# BeanCounter_V10.net
KiCad netlist of a schematic drawn in EAGLE
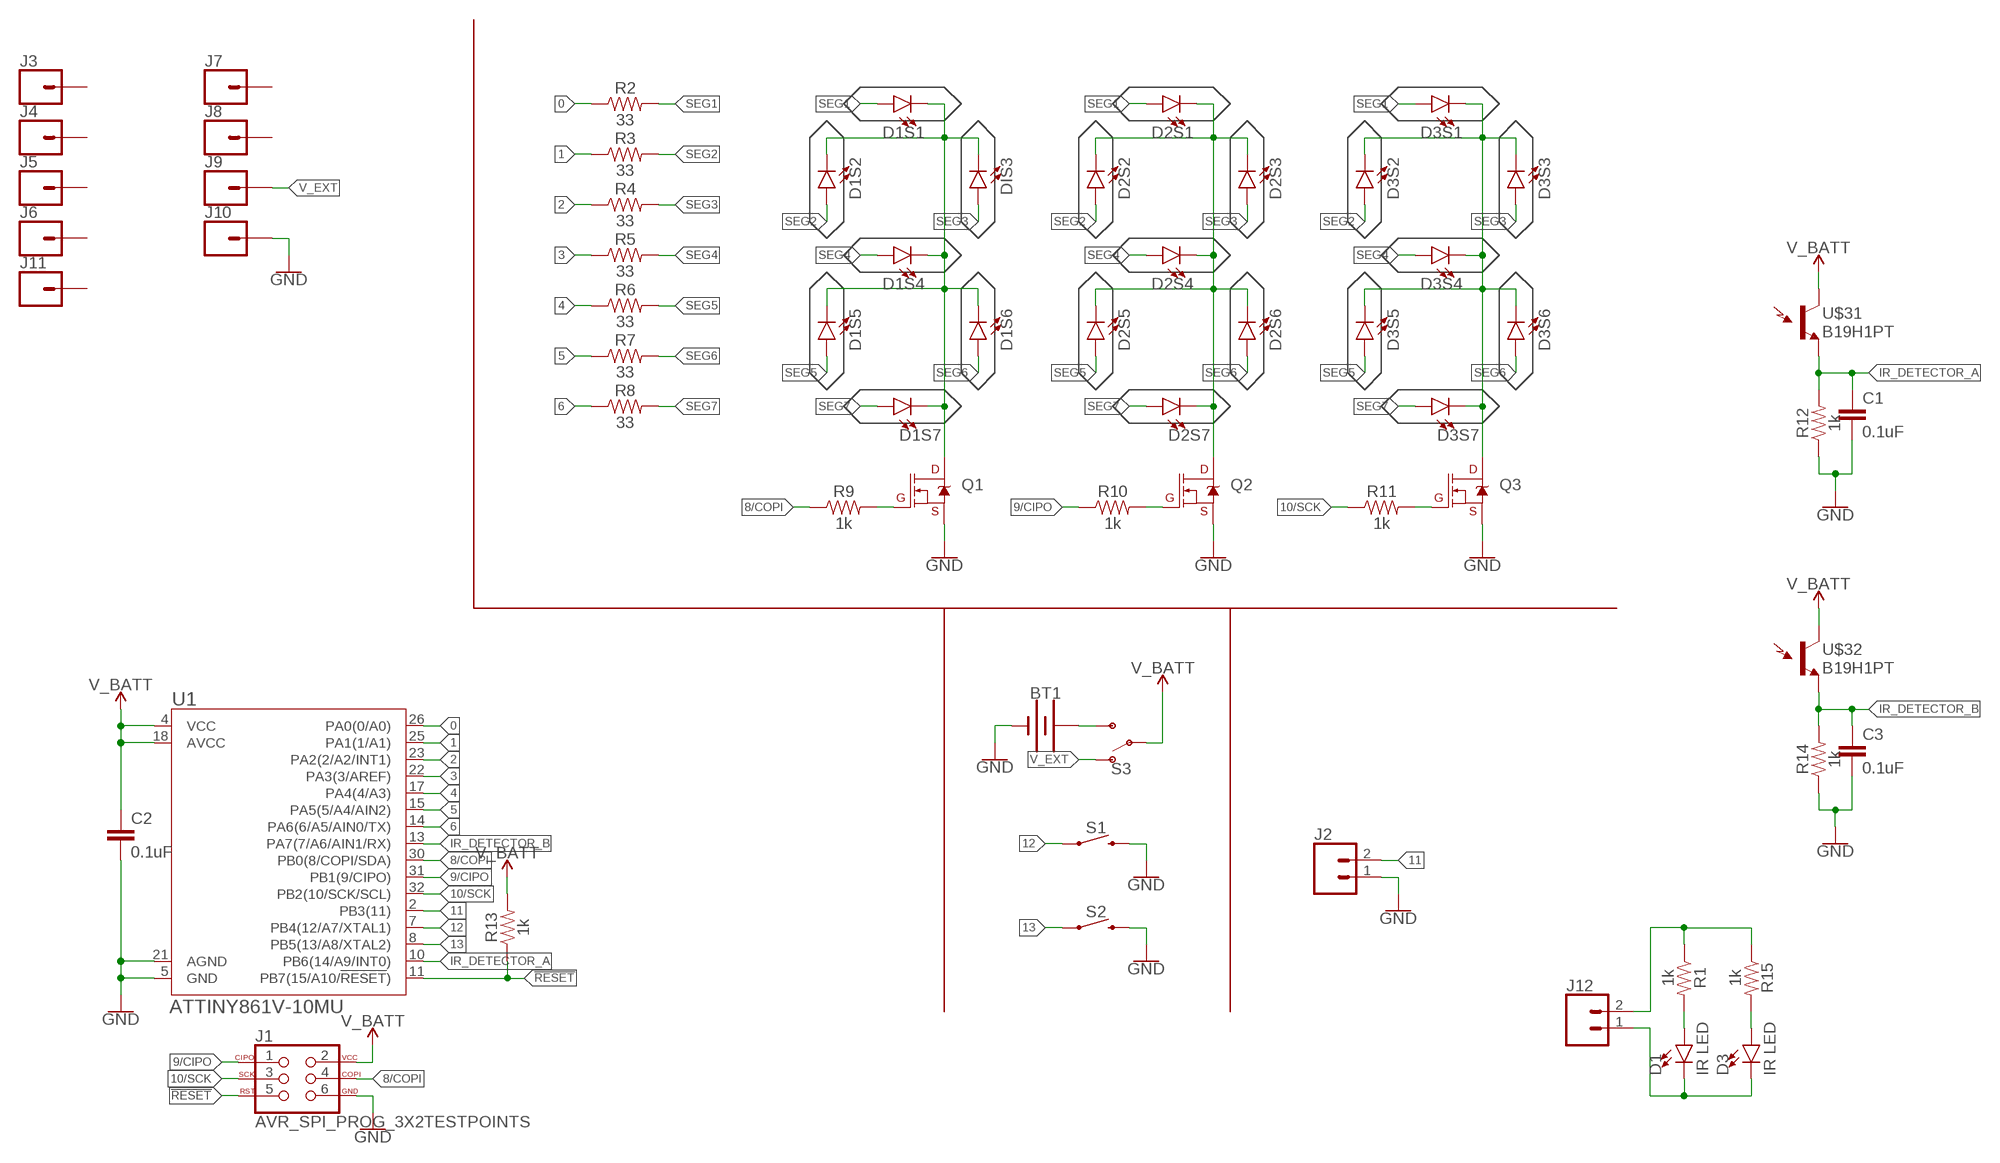
[diagram p0: schematic, sheet 1]

(export (version "E")
  (design (tool "Eeschema 10.0.6"))
  (components
    (comp (ref "BT1")
      (value "BATTERY-20MM_SMD_4LEGS_OVERPASTE_INNER")
      (footprint "eagle-import:BATTCON_20MM_4LEGS_OVERPASTE_INNER")
      (libsource (lib "eagle-import") (part "BATTERY-20MM_SMD_4LEGS_OVERPASTE_INNER"))
    )
    (comp (ref "C1")
      (value "0.1uF")
      (footprint "eagle-import:0603")
      (libsource (lib "eagle-import") (part "0.1UF-0603-25V-(+80/-20%)"))
    )
    (comp (ref "C2")
      (value "0.1uF")
      (footprint "eagle-import:0603")
      (libsource (lib "eagle-import") (part "0.1UF-0603-25V-(+80/-20%)"))
    )
    (comp (ref "C3")
      (value "0.1uF")
      (footprint "eagle-import:0603")
      (libsource (lib "eagle-import") (part "0.1UF-0603-25V-(+80/-20%)"))
    )
    (comp (ref "D1")
      (value "IR LED")
      (footprint "eagle-import:LED-0603")
      (libsource (lib "eagle-import") (part "LED-IR0603"))
    )
    (comp (ref "D1S1")
      (value "LED0603")
      (footprint "eagle-import:LED-0603")
      (libsource (lib "eagle-import") (part "LED0603"))
    )
    (comp (ref "D1S2")
      (value "LED0603")
      (footprint "eagle-import:LED-0603")
      (libsource (lib "eagle-import") (part "LED0603"))
    )
    (comp (ref "D1S4")
      (value "LED0603")
      (footprint "eagle-import:LED-0603")
      (libsource (lib "eagle-import") (part "LED0603"))
    )
    (comp (ref "D1S5")
      (value "LED0603")
      (footprint "eagle-import:LED-0603")
      (libsource (lib "eagle-import") (part "LED0603"))
    )
    (comp (ref "D1S6")
      (value "LED0603")
      (footprint "eagle-import:LED-0603")
      (libsource (lib "eagle-import") (part "LED0603"))
    )
    (comp (ref "D1S7")
      (value "LED0603")
      (footprint "eagle-import:LED-0603")
      (libsource (lib "eagle-import") (part "LED0603"))
    )
    (comp (ref "D2S1")
      (value "LED0603")
      (footprint "eagle-import:LED-0603")
      (libsource (lib "eagle-import") (part "LED0603"))
    )
    (comp (ref "D2S2")
      (value "LED0603")
      (footprint "eagle-import:LED-0603")
      (libsource (lib "eagle-import") (part "LED0603"))
    )
    (comp (ref "D2S3")
      (value "LED0603")
      (footprint "eagle-import:LED-0603")
      (libsource (lib "eagle-import") (part "LED0603"))
    )
    (comp (ref "D2S4")
      (value "LED0603")
      (footprint "eagle-import:LED-0603")
      (libsource (lib "eagle-import") (part "LED0603"))
    )
    (comp (ref "D2S5")
      (value "LED0603")
      (footprint "eagle-import:LED-0603")
      (libsource (lib "eagle-import") (part "LED0603"))
    )
    (comp (ref "D2S6")
      (value "LED0603")
      (footprint "eagle-import:LED-0603")
      (libsource (lib "eagle-import") (part "LED0603"))
    )
    (comp (ref "D2S7")
      (value "LED0603")
      (footprint "eagle-import:LED-0603")
      (libsource (lib "eagle-import") (part "LED0603"))
    )
    (comp (ref "D3")
      (value "IR LED")
      (footprint "eagle-import:LED-0603")
      (libsource (lib "eagle-import") (part "LED-IR0603"))
    )
    (comp (ref "D3S1")
      (value "LED0603")
      (footprint "eagle-import:LED-0603")
      (libsource (lib "eagle-import") (part "LED0603"))
    )
    (comp (ref "D3S2")
      (value "LED0603")
      (footprint "eagle-import:LED-0603")
      (libsource (lib "eagle-import") (part "LED0603"))
    )
    (comp (ref "D3S3")
      (value "LED0603")
      (footprint "eagle-import:LED-0603")
      (libsource (lib "eagle-import") (part "LED0603"))
    )
    (comp (ref "D3S4")
      (value "LED0603")
      (footprint "eagle-import:LED-0603")
      (libsource (lib "eagle-import") (part "LED0603"))
    )
    (comp (ref "D3S5")
      (value "LED0603")
      (footprint "eagle-import:LED-0603")
      (libsource (lib "eagle-import") (part "LED0603"))
    )
    (comp (ref "D3S6")
      (value "LED0603")
      (footprint "eagle-import:LED-0603")
      (libsource (lib "eagle-import") (part "LED0603"))
    )
    (comp (ref "D3S7")
      (value "LED0603")
      (footprint "eagle-import:LED-0603")
      (libsource (lib "eagle-import") (part "LED0603"))
    )
    (comp (ref "DIS3")
      (value "LED0603")
      (footprint "eagle-import:LED-0603")
      (libsource (lib "eagle-import") (part "LED0603"))
    )
    (comp (ref "J1")
      (value "AVR_SPI_PROG_3X2TESTPOINTS")
      (footprint "eagle-import:2X3_TEST_POINTS")
      (libsource (lib "eagle-import") (part "AVR_SPI_PROG_3X2TESTPOINTS"))
    )
    (comp (ref "J2")
      (value "CONN_02")
      (footprint "eagle-import:1X02")
      (libsource (lib "eagle-import") (part "CONN_02"))
    )
    (comp (ref "J3")
      (value "CONN_01")
      (footprint "eagle-import:1X01")
      (libsource (lib "eagle-import") (part "CONN_01"))
    )
    (comp (ref "J4")
      (value "CONN_01")
      (footprint "eagle-import:1X01")
      (libsource (lib "eagle-import") (part "CONN_01"))
    )
    (comp (ref "J5")
      (value "CONN_01")
      (footprint "eagle-import:1X01")
      (libsource (lib "eagle-import") (part "CONN_01"))
    )
    (comp (ref "J6")
      (value "CONN_01")
      (footprint "eagle-import:1X01")
      (libsource (lib "eagle-import") (part "CONN_01"))
    )
    (comp (ref "J7")
      (value "CONN_01")
      (footprint "eagle-import:1X01")
      (libsource (lib "eagle-import") (part "CONN_01"))
    )
    (comp (ref "J8")
      (value "CONN_01")
      (footprint "eagle-import:1X01")
      (libsource (lib "eagle-import") (part "CONN_01"))
    )
    (comp (ref "J9")
      (value "CONN_01")
      (footprint "eagle-import:1X01")
      (libsource (lib "eagle-import") (part "CONN_01"))
    )
    (comp (ref "J10")
      (value "CONN_01")
      (footprint "eagle-import:1X01")
      (libsource (lib "eagle-import") (part "CONN_01"))
    )
    (comp (ref "J11")
      (value "CONN_01")
      (footprint "eagle-import:1X01")
      (libsource (lib "eagle-import") (part "CONN_01"))
    )
    (comp (ref "J12")
      (value "CONN_02")
      (footprint "eagle-import:1X02")
      (libsource (lib "eagle-import") (part "CONN_02"))
    )
    (comp (ref "Q1")
      (value "220mA/50V/3.5Ω")
      (footprint "eagle-import:SOT23-3")
      (libsource (lib "eagle-import") (part "MOSFET-NCH-BSS138"))
    )
    (comp (ref "Q2")
      (value "220mA/50V/3.5Ω")
      (footprint "eagle-import:SOT23-3")
      (libsource (lib "eagle-import") (part "MOSFET-NCH-BSS138"))
    )
    (comp (ref "Q3")
      (value "220mA/50V/3.5Ω")
      (footprint "eagle-import:SOT23-3")
      (libsource (lib "eagle-import") (part "MOSFET-NCH-BSS138"))
    )
    (comp (ref "R1")
      (value "1k")
      (footprint "eagle-import:0603")
      (libsource (lib "eagle-import") (part "1KOHM-0603-1/10W-1%"))
    )
    (comp (ref "R2")
      (value "33")
      (footprint "eagle-import:0603")
      (libsource (lib "eagle-import") (part "33OHM-0603-1/10W-1%"))
    )
    (comp (ref "R3")
      (value "33")
      (footprint "eagle-import:0603")
      (libsource (lib "eagle-import") (part "33OHM-0603-1/10W-1%"))
    )
    (comp (ref "R4")
      (value "33")
      (footprint "eagle-import:0603")
      (libsource (lib "eagle-import") (part "33OHM-0603-1/10W-1%"))
    )
    (comp (ref "R5")
      (value "33")
      (footprint "eagle-import:0603")
      (libsource (lib "eagle-import") (part "33OHM-0603-1/10W-1%"))
    )
    (comp (ref "R6")
      (value "33")
      (footprint "eagle-import:0603")
      (libsource (lib "eagle-import") (part "33OHM-0603-1/10W-1%"))
    )
    (comp (ref "R7")
      (value "33")
      (footprint "eagle-import:0603")
      (libsource (lib "eagle-import") (part "33OHM-0603-1/10W-1%"))
    )
    (comp (ref "R8")
      (value "33")
      (footprint "eagle-import:0603")
      (libsource (lib "eagle-import") (part "33OHM-0603-1/10W-1%"))
    )
    (comp (ref "R9")
      (value "1k")
      (footprint "eagle-import:0603")
      (libsource (lib "eagle-import") (part "1KOHM-0603-1/10W-1%"))
    )
    (comp (ref "R10")
      (value "1k")
      (footprint "eagle-import:0603")
      (libsource (lib "eagle-import") (part "1KOHM-0603-1/10W-1%"))
    )
    (comp (ref "R11")
      (value "1k")
      (footprint "eagle-import:0603")
      (libsource (lib "eagle-import") (part "1KOHM-0603-1/10W-1%"))
    )
    (comp (ref "R12")
      (value "1k")
      (footprint "eagle-import:0603")
      (libsource (lib "eagle-import") (part "1KOHM-0603-1/10W-1%"))
    )
    (comp (ref "R13")
      (value "1k")
      (footprint "eagle-import:0603")
      (libsource (lib "eagle-import") (part "1KOHM-0603-1/10W-1%"))
    )
    (comp (ref "R14")
      (value "1k")
      (footprint "eagle-import:0603")
      (libsource (lib "eagle-import") (part "1KOHM-0603-1/10W-1%"))
    )
    (comp (ref "R15")
      (value "1k")
      (footprint "eagle-import:0603")
      (libsource (lib "eagle-import") (part "1KOHM-0603-1/10W-1%"))
    )
    (comp (ref "S1")
      (value "MOMENTARY-SWITCH-SPST-SMD-5.2MM-TALL")
      (footprint "eagle-import:TACTILE_SWITCH_SMD_5.2MM")
      (libsource (lib "eagle-import") (part "MOMENTARY-SWITCH-SPST-SMD-5.2MM-TALL"))
    )
    (comp (ref "S2")
      (value "MOMENTARY-SWITCH-SPST-SMD-5.2MM-TALL")
      (footprint "eagle-import:TACTILE_SWITCH_SMD_5.2MM")
      (libsource (lib "eagle-import") (part "MOMENTARY-SWITCH-SPST-SMD-5.2MM-TALL"))
    )
    (comp (ref "S3")
      (value "SWITCH-SPDT-SMD-RIGHT-ANGLE")
      (footprint "eagle-import:SWITCH_SPST_SMD_A")
      (libsource (lib "eagle-import") (part "SWITCH-SPDT-SMD-RIGHT-ANGLE"))
    )
    (comp (ref "U$31")
      (value "B19H1PT")
      (footprint "eagle-import:HARVATEK_DETECTOR")
      (libsource (lib "eagle-import") (part "B19H1PT"))
    )
    (comp (ref "U$32")
      (value "B19H1PT")
      (footprint "eagle-import:HARVATEK_DETECTOR")
      (libsource (lib "eagle-import") (part "B19H1PT"))
    )
    (comp (ref "U1")
      (value "ATTINY861V-10MU")
      (footprint "eagle-import:32M1-A_ATM")
      (fields (field (name "COPYRIGHT") "Copyright (C) 2021 Ultra Librarian. All rights reserved."))
      (libsource (lib "eagle-import") (part "ATTINY861V-10MU"))
    )
  )
  (nets
    (net (code "1") (name "/~{RESET}") (class "Default")
      (node (ref "J1") (pin "5") (pinfunction "5_5") (pintype "passive"))
      (node (ref "R13") (pin "1") (pinfunction "1_1") (pintype "passive"))
      (node (ref "U1") (pin "11") (pinfunction "PB7(15/A10/~{RESET})_11") (pintype "bidirectional"))
    )
    (net (code "2") (name "0") (class "Default")
      (node (ref "R2") (pin "1") (pinfunction "1_1") (pintype "passive"))
      (node (ref "U1") (pin "26") (pinfunction "PA0(0/A0)_26") (pintype "bidirectional"))
    )
    (net (code "3") (name "1") (class "Default")
      (node (ref "R3") (pin "1") (pinfunction "1_1") (pintype "passive"))
      (node (ref "U1") (pin "25") (pinfunction "PA1(1/A1)_25") (pintype "bidirectional"))
    )
    (net (code "4") (name "2") (class "Default")
      (node (ref "R4") (pin "1") (pinfunction "1_1") (pintype "passive"))
      (node (ref "U1") (pin "23") (pinfunction "PA2(2/A2/INT1)_23") (pintype "bidirectional"))
    )
    (net (code "5") (name "3") (class "Default")
      (node (ref "R5") (pin "1") (pinfunction "1_1") (pintype "passive"))
      (node (ref "U1") (pin "22") (pinfunction "PA3(3/AREF)_22") (pintype "bidirectional"))
    )
    (net (code "6") (name "4") (class "Default")
      (node (ref "R6") (pin "1") (pinfunction "1_1") (pintype "passive"))
      (node (ref "U1") (pin "17") (pinfunction "PA4(4/A3)_17") (pintype "bidirectional"))
    )
    (net (code "7") (name "5") (class "Default")
      (node (ref "R7") (pin "1") (pinfunction "1_1") (pintype "passive"))
      (node (ref "U1") (pin "15") (pinfunction "PA5(5/A4/AIN2)_15") (pintype "bidirectional"))
    )
    (net (code "8") (name "6") (class "Default")
      (node (ref "R8") (pin "1") (pinfunction "1_1") (pintype "passive"))
      (node (ref "U1") (pin "14") (pinfunction "PA6(6/A5/AIN0/TX)_14") (pintype "bidirectional"))
    )
    (net (code "9") (name "8{slash}COPI") (class "Default")
      (node (ref "J1") (pin "4") (pinfunction "4_4") (pintype "passive"))
      (node (ref "R9") (pin "1") (pinfunction "1_1") (pintype "passive"))
      (node (ref "U1") (pin "30") (pinfunction "PB0(8/COPI/SDA)_30") (pintype "bidirectional"))
    )
    (net (code "10") (name "9{slash}CIPO") (class "Default")
      (node (ref "J1") (pin "1") (pinfunction "1_1") (pintype "passive"))
      (node (ref "R10") (pin "1") (pinfunction "1_1") (pintype "passive"))
      (node (ref "U1") (pin "31") (pinfunction "PB1(9/CIPO)_31") (pintype "bidirectional"))
    )
    (net (code "11") (name "10{slash}SCK") (class "Default")
      (node (ref "J1") (pin "3") (pinfunction "3_3") (pintype "passive"))
      (node (ref "R11") (pin "1") (pinfunction "1_1") (pintype "passive"))
      (node (ref "U1") (pin "32") (pinfunction "PB2(10/SCK/SCL)_32") (pintype "bidirectional"))
    )
    (net (code "12") (name "11") (class "Default")
      (node (ref "J2") (pin "2") (pinfunction "2_2") (pintype "passive"))
      (node (ref "U1") (pin "2") (pinfunction "PB3(11)_2") (pintype "bidirectional"))
    )
    (net (code "13") (name "12") (class "Default")
      (node (ref "S1") (pin "1") (pinfunction "1_1") (pintype "passive"))
      (node (ref "U1") (pin "7") (pinfunction "PB4(12/A7/XTAL1)_7") (pintype "bidirectional"))
    )
    (net (code "14") (name "13") (class "Default")
      (node (ref "S2") (pin "1") (pinfunction "1_1") (pintype "passive"))
      (node (ref "U1") (pin "8") (pinfunction "PB5(13/A8/XTAL2)_8") (pintype "bidirectional"))
    )
    (net (code "15") (name "GND") (class "Default")
      (node (ref "BT1") (pin "2") (pinfunction "-_2") (pintype "power_in"))
      (node (ref "C1") (pin "2") (pinfunction "2_2") (pintype "passive"))
      (node (ref "C2") (pin "2") (pinfunction "2_2") (pintype "passive"))
      (node (ref "C3") (pin "2") (pinfunction "2_2") (pintype "passive"))
      (node (ref "J1") (pin "6") (pinfunction "6_6") (pintype "passive"))
      (node (ref "J10") (pin "1") (pinfunction "1_1") (pintype "passive"))
      (node (ref "J2") (pin "1") (pinfunction "1_1") (pintype "passive"))
      (node (ref "Q1") (pin "2") (pinfunction "S_2") (pintype "bidirectional"))
      (node (ref "Q2") (pin "2") (pinfunction "S_2") (pintype "bidirectional"))
      (node (ref "Q3") (pin "2") (pinfunction "S_2") (pintype "bidirectional"))
      (node (ref "R12") (pin "1") (pinfunction "1_1") (pintype "passive"))
      (node (ref "R14") (pin "1") (pinfunction "1_1") (pintype "passive"))
      (node (ref "S1") (pin "3") (pinfunction "2_3") (pintype "passive"))
      (node (ref "S2") (pin "3") (pinfunction "2_3") (pintype "passive"))
      (node (ref "U1") (pin "21") (pinfunction "AGND_21") (pintype "power_in"))
      (node (ref "U1") (pin "5") (pinfunction "GND_5") (pintype "power_in"))
    )
    (net (code "16") (name "IR_DETECTOR_A") (class "Default")
      (node (ref "C1") (pin "1") (pinfunction "1_1") (pintype "passive"))
      (node (ref "R12") (pin "2") (pinfunction "2_2") (pintype "passive"))
      (node (ref "U$31") (pin "P$2") (pinfunction "E1_P$2") (pintype "passive"))
      (node (ref "U1") (pin "10") (pinfunction "PB6(14/A9/INT0)_10") (pintype "bidirectional"))
    )
    (net (code "17") (name "IR_DETECTOR_B") (class "Default")
      (node (ref "C3") (pin "1") (pinfunction "1_1") (pintype "passive"))
      (node (ref "R14") (pin "2") (pinfunction "2_2") (pintype "passive"))
      (node (ref "U$32") (pin "P$2") (pinfunction "E1_P$2") (pintype "passive"))
      (node (ref "U1") (pin "13") (pinfunction "PA7(7/A6/AIN1/RX)_13") (pintype "bidirectional"))
    )
    (net (code "18") (name "Net-(BT1-+)") (class "Default")
      (node (ref "BT1") (pin "1") (pinfunction "+_1") (pintype "power_in"))
      (node (ref "S3") (pin "3") (pinfunction "S_3") (pintype "passive"))
    )
    (net (code "19") (name "Net-(D1-PadA)") (class "Default")
      (node (ref "D1") (pin "A") (pinfunction "A_A") (pintype "passive"))
      (node (ref "R1") (pin "2") (pinfunction "2_2") (pintype "passive"))
    )
    (net (code "20") (name "Net-(D1-PadC)") (class "Default")
      (node (ref "D1") (pin "C") (pinfunction "C_C") (pintype "passive"))
      (node (ref "D3") (pin "C") (pinfunction "C_C") (pintype "passive"))
      (node (ref "J12") (pin "1") (pinfunction "1_1") (pintype "passive"))
    )
    (net (code "21") (name "Net-(D3-PadA)") (class "Default")
      (node (ref "D3") (pin "A") (pinfunction "A_A") (pintype "passive"))
      (node (ref "R15") (pin "2") (pinfunction "2_2") (pintype "passive"))
    )
    (net (code "22") (name "Net-(J12-Pad2)") (class "Default")
      (node (ref "J12") (pin "2") (pinfunction "2_2") (pintype "passive"))
      (node (ref "R1") (pin "1") (pinfunction "1_1") (pintype "passive"))
      (node (ref "R15") (pin "1") (pinfunction "1_1") (pintype "passive"))
    )
    (net (code "23") (name "Net-(Q1-D)") (class "Default")
      (node (ref "D1S1") (pin "C") (pinfunction "C_C") (pintype "passive"))
      (node (ref "D1S2") (pin "C") (pinfunction "C_C") (pintype "passive"))
      (node (ref "D1S4") (pin "C") (pinfunction "C_C") (pintype "passive"))
      (node (ref "D1S5") (pin "C") (pinfunction "C_C") (pintype "passive"))
      (node (ref "D1S6") (pin "C") (pinfunction "C_C") (pintype "passive"))
      (node (ref "D1S7") (pin "C") (pinfunction "C_C") (pintype "passive"))
      (node (ref "DIS3") (pin "C") (pinfunction "C_C") (pintype "passive"))
      (node (ref "Q1") (pin "3") (pinfunction "D_3") (pintype "bidirectional"))
    )
    (net (code "24") (name "Net-(Q1-G)") (class "Default")
      (node (ref "Q1") (pin "1") (pinfunction "G_1") (pintype "bidirectional"))
      (node (ref "R9") (pin "2") (pinfunction "2_2") (pintype "passive"))
    )
    (net (code "25") (name "Net-(Q2-D)") (class "Default")
      (node (ref "D2S1") (pin "C") (pinfunction "C_C") (pintype "passive"))
      (node (ref "D2S2") (pin "C") (pinfunction "C_C") (pintype "passive"))
      (node (ref "D2S3") (pin "C") (pinfunction "C_C") (pintype "passive"))
      (node (ref "D2S4") (pin "C") (pinfunction "C_C") (pintype "passive"))
      (node (ref "D2S5") (pin "C") (pinfunction "C_C") (pintype "passive"))
      (node (ref "D2S6") (pin "C") (pinfunction "C_C") (pintype "passive"))
      (node (ref "D2S7") (pin "C") (pinfunction "C_C") (pintype "passive"))
      (node (ref "Q2") (pin "3") (pinfunction "D_3") (pintype "bidirectional"))
    )
    (net (code "26") (name "Net-(Q2-G)") (class "Default")
      (node (ref "Q2") (pin "1") (pinfunction "G_1") (pintype "bidirectional"))
      (node (ref "R10") (pin "2") (pinfunction "2_2") (pintype "passive"))
    )
    (net (code "27") (name "Net-(Q3-D)") (class "Default")
      (node (ref "D3S1") (pin "C") (pinfunction "C_C") (pintype "passive"))
      (node (ref "D3S2") (pin "C") (pinfunction "C_C") (pintype "passive"))
      (node (ref "D3S3") (pin "C") (pinfunction "C_C") (pintype "passive"))
      (node (ref "D3S4") (pin "C") (pinfunction "C_C") (pintype "passive"))
      (node (ref "D3S5") (pin "C") (pinfunction "C_C") (pintype "passive"))
      (node (ref "D3S6") (pin "C") (pinfunction "C_C") (pintype "passive"))
      (node (ref "D3S7") (pin "C") (pinfunction "C_C") (pintype "passive"))
      (node (ref "Q3") (pin "3") (pinfunction "D_3") (pintype "bidirectional"))
    )
    (net (code "28") (name "Net-(Q3-G)") (class "Default")
      (node (ref "Q3") (pin "1") (pinfunction "G_1") (pintype "bidirectional"))
      (node (ref "R11") (pin "2") (pinfunction "2_2") (pintype "passive"))
    )
    (net (code "29") (name "SEG1") (class "Default")
      (node (ref "D1S1") (pin "A") (pinfunction "A_A") (pintype "passive"))
      (node (ref "D2S1") (pin "A") (pinfunction "A_A") (pintype "passive"))
      (node (ref "D3S1") (pin "A") (pinfunction "A_A") (pintype "passive"))
      (node (ref "R2") (pin "2") (pinfunction "2_2") (pintype "passive"))
    )
    (net (code "30") (name "SEG2") (class "Default")
      (node (ref "D1S2") (pin "A") (pinfunction "A_A") (pintype "passive"))
      (node (ref "D2S2") (pin "A") (pinfunction "A_A") (pintype "passive"))
      (node (ref "D3S2") (pin "A") (pinfunction "A_A") (pintype "passive"))
      (node (ref "R3") (pin "2") (pinfunction "2_2") (pintype "passive"))
    )
    (net (code "31") (name "SEG3") (class "Default")
      (node (ref "D2S3") (pin "A") (pinfunction "A_A") (pintype "passive"))
      (node (ref "D3S3") (pin "A") (pinfunction "A_A") (pintype "passive"))
      (node (ref "DIS3") (pin "A") (pinfunction "A_A") (pintype "passive"))
      (node (ref "R4") (pin "2") (pinfunction "2_2") (pintype "passive"))
    )
    (net (code "32") (name "SEG4") (class "Default")
      (node (ref "D1S4") (pin "A") (pinfunction "A_A") (pintype "passive"))
      (node (ref "D2S4") (pin "A") (pinfunction "A_A") (pintype "passive"))
      (node (ref "D3S4") (pin "A") (pinfunction "A_A") (pintype "passive"))
      (node (ref "R5") (pin "2") (pinfunction "2_2") (pintype "passive"))
    )
    (net (code "33") (name "SEG5") (class "Default")
      (node (ref "D1S5") (pin "A") (pinfunction "A_A") (pintype "passive"))
      (node (ref "D2S5") (pin "A") (pinfunction "A_A") (pintype "passive"))
      (node (ref "D3S5") (pin "A") (pinfunction "A_A") (pintype "passive"))
      (node (ref "R6") (pin "2") (pinfunction "2_2") (pintype "passive"))
    )
    (net (code "34") (name "SEG6") (class "Default")
      (node (ref "D1S6") (pin "A") (pinfunction "A_A") (pintype "passive"))
      (node (ref "D2S6") (pin "A") (pinfunction "A_A") (pintype "passive"))
      (node (ref "D3S6") (pin "A") (pinfunction "A_A") (pintype "passive"))
      (node (ref "R7") (pin "2") (pinfunction "2_2") (pintype "passive"))
    )
    (net (code "35") (name "SEG7") (class "Default")
      (node (ref "D1S7") (pin "A") (pinfunction "A_A") (pintype "passive"))
      (node (ref "D2S7") (pin "A") (pinfunction "A_A") (pintype "passive"))
      (node (ref "D3S7") (pin "A") (pinfunction "A_A") (pintype "passive"))
      (node (ref "R8") (pin "2") (pinfunction "2_2") (pintype "passive"))
    )
    (net (code "36") (name "V_BATT") (class "Default")
      (node (ref "C2") (pin "1") (pinfunction "1_1") (pintype "passive"))
      (node (ref "J1") (pin "2") (pinfunction "2_2") (pintype "passive"))
      (node (ref "R13") (pin "2") (pinfunction "2_2") (pintype "passive"))
      (node (ref "S3") (pin "2") (pinfunction "P_2") (pintype "passive"))
      (node (ref "U$31") (pin "P$1") (pinfunction "C1_P$1") (pintype "passive"))
      (node (ref "U$32") (pin "P$1") (pinfunction "C1_P$1") (pintype "passive"))
      (node (ref "U1") (pin "18") (pinfunction "AVCC_18") (pintype "power_in"))
      (node (ref "U1") (pin "4") (pinfunction "VCC_4") (pintype "power_in"))
    )
    (net (code "37") (name "V_EXT") (class "Default")
      (node (ref "J9") (pin "1") (pinfunction "1_1") (pintype "passive"))
      (node (ref "S3") (pin "1") (pinfunction "O_1") (pintype "passive"))
    )
    (net (code "38") (name "unconnected-(J3-Pad1)") (class "Default")
      (node (ref "J3") (pin "1") (pinfunction "1_1") (pintype "passive"))
    )
    (net (code "39") (name "unconnected-(J4-Pad1)") (class "Default")
      (node (ref "J4") (pin "1") (pinfunction "1_1") (pintype "passive"))
    )
    (net (code "40") (name "unconnected-(J5-Pad1)") (class "Default")
      (node (ref "J5") (pin "1") (pinfunction "1_1") (pintype "passive"))
    )
    (net (code "41") (name "unconnected-(J6-Pad1)") (class "Default")
      (node (ref "J6") (pin "1") (pinfunction "1_1") (pintype "passive"))
    )
    (net (code "42") (name "unconnected-(J7-Pad1)") (class "Default")
      (node (ref "J7") (pin "1") (pinfunction "1_1") (pintype "passive"))
    )
    (net (code "43") (name "unconnected-(J8-Pad1)") (class "Default")
      (node (ref "J8") (pin "1") (pinfunction "1_1") (pintype "passive"))
    )
    (net (code "44") (name "unconnected-(J11-Pad1)") (class "Default")
      (node (ref "J11") (pin "1") (pinfunction "1_1") (pintype "passive"))
    )
  )
)
